# Arduino__Connectors.net
KiCad netlist of a schematic drawn in Altium Designer
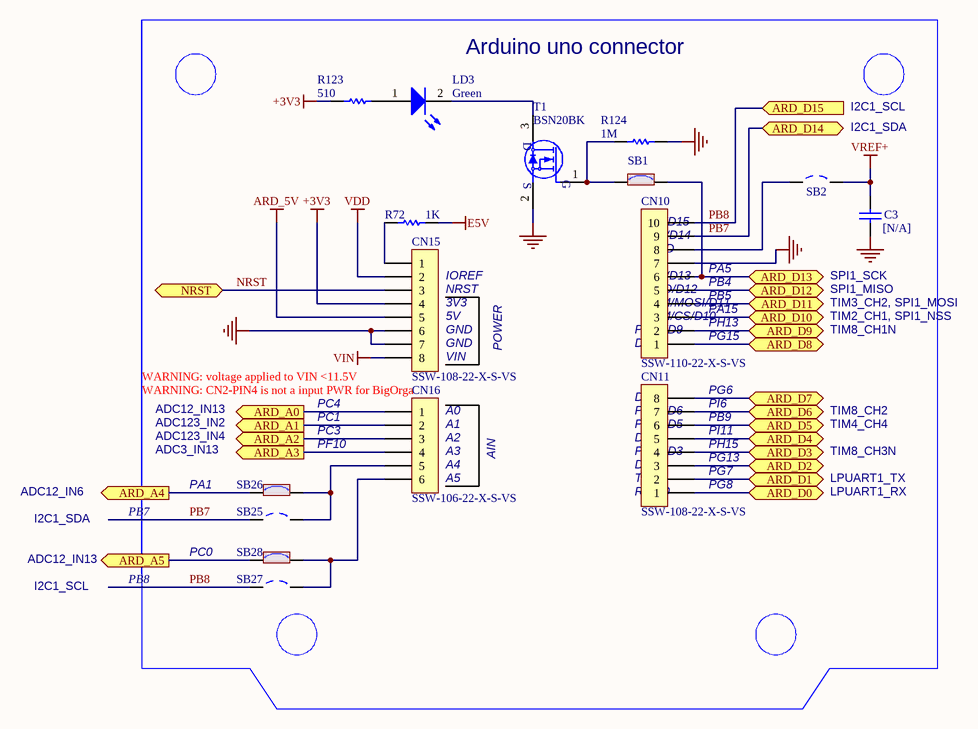
[diagram p0: Arduino_ Connectors.SchDoc]

(export (version "E")
  (design (tool "Eeschema 10.0.6"))
  (components
    (comp (ref "C3")
      (value "[N/A]")
      (footprint "0603C")
      (description "Capacitor,100nF,10%,16V,X7R,0603,YAGEO")
      (fields (field (name "PUBLISHER") "Altium Limited"))
      (libsource (lib "Miscellaneous Devices") (part "Cap"))
    )
    (comp (ref "CN10")
      (value "SSW-110-22-X-S-VS")
      (footprint "SSW-110-22-X-S-VS")
      (description "Header, 10-Pin, Single row,female")
      (fields (field (name "PUBLISHER") "Altium Limited"))
      (libsource (lib "Nucleo_64") (part "Header 10X1_Female"))
    )
    (comp (ref "CN11")
      (value "SSW-108-22-X-S-VS")
      (footprint "SSW-108-22-X-S-VS")
      (description "Header, 8-Pin, Single row,female")
      (fields (field (name "PUBLISHER") "Altium Limited"))
      (libsource (lib "Nucleo_64") (part "Header 8X1_Female"))
    )
    (comp (ref "CN15")
      (value "SSW-108-22-X-S-VS")
      (footprint "SSW-108-22-X-S-VS")
      (description "Header, 8-Pin, Single row,female")
      (fields (field (name "PUBLISHER") "Altium Limited"))
      (libsource (lib "") (part "Header 8X1_Female_1"))
    )
    (comp (ref "CN16")
      (value "SSW-106-22-X-S-VS")
      (footprint "SSW-106-22-X-S-VS")
      (description "Header, 6-Pin, Single row,female")
      (fields (field (name "PUBLISHER") "Altium Limited"))
      (libsource (lib "Nucleo_64") (part "Header 6X1_Female"))
    )
    (comp (ref "LD3")
      (value "19-213SY6C/S530-E2/TR8LED")
      (footprint "0603D")
      (description "LED,Green,0603")
      (fields (field (name "CORLOR") "Green") (field (name "PUBLISHER") "Altium Limited"))
      (libsource (lib "Miscellaneous Devices") (part "LED2"))
    )
    (comp (ref "R72")
      (value "1K")
      (footprint "0603R")
      (description "Resistor,1K,0603,1%")
      (fields (field (name "PUBLISHER") "Altium Limited"))
      (libsource (lib "Miscellaneous Devices") (part "res1"))
    )
    (comp (ref "R123")
      (value "510")
      (footprint "0603R")
      (description "Resistor, 510R , 0603,1%,YAGEO")
      (fields (field (name "Comment") "RC0603JR-07510RL") (field (name "PUBLISHER") "Altium Limited"))
      (libsource (lib "Miscellaneous Devices") (part "res1"))
    )
    (comp (ref "R124")
      (value "1M")
      (footprint "0603R")
      (description "Resistor, 1M , 0603")
      (fields (field (name "PUBLISHER") "Altium Limited"))
      (libsource (lib "Miscellaneous Devices") (part "res1"))
    )
    (comp (ref "SB1")
      (value "Solder Bridge ON")
      (footprint "SB_0603")
      (libsource (lib "MCD_TOOLS") (part "SB_ON"))
    )
    (comp (ref "SB2")
      (value "Solder Bridge OFF")
      (footprint "SB_0603")
      (libsource (lib "MCD_TOOLS") (part "SB_OFF"))
    )
    (comp (ref "SB25")
      (value "Solder Bridge OFF")
      (footprint "SB_0603")
      (libsource (lib "MCD_TOOLS") (part "SB_OFF"))
    )
    (comp (ref "SB26")
      (value "Solder Bridge ON")
      (footprint "SB_0603")
      (libsource (lib "MCD_TOOLS") (part "SB_ON"))
    )
    (comp (ref "SB27")
      (value "Solder Bridge OFF")
      (footprint "SB_0603")
      (libsource (lib "MCD_TOOLS") (part "SB_OFF"))
    )
    (comp (ref "SB28")
      (value "Solder Bridge ON")
      (footprint "SB_0603")
      (libsource (lib "MCD_TOOLS") (part "SB_ON"))
    )
    (comp (ref "T1") (value "BSN20BK") (footprint "SOT-23") (libsource (lib "MB525") (part "2N7000")))
  )
  (nets
    (net (code "1") (name "+3V3") (class "Default")
      (node (ref "CN15") (pin "4") (pinfunction "4_4") (pintype "passive"))
      (node (ref "R123") (pin "1") (pinfunction "1_1") (pintype "passive"))
    )
    (net (code "2") (name "/ARD_A0") (class "Default")
      (node (ref "CN16") (pin "1") (pinfunction "1_1") (pintype "passive"))
    )
    (net (code "3") (name "/ARD_A1") (class "Default")
      (node (ref "CN16") (pin "2") (pinfunction "2_2") (pintype "passive"))
    )
    (net (code "4") (name "/ARD_A2") (class "Default")
      (node (ref "CN16") (pin "3") (pinfunction "3_3") (pintype "passive"))
    )
    (net (code "5") (name "/ARD_A3") (class "Default")
      (node (ref "CN16") (pin "4") (pinfunction "4_4") (pintype "passive"))
    )
    (net (code "6") (name "/ARD_A4") (class "Default")
      (node (ref "SB26") (pin "1") (pinfunction "1_1") (pintype "passive"))
    )
    (net (code "7") (name "/ARD_A5") (class "Default")
      (node (ref "SB28") (pin "1") (pinfunction "1_1") (pintype "passive"))
    )
    (net (code "8") (name "/ARD_D0") (class "Default")
      (node (ref "CN11") (pin "1") (pinfunction "1_1") (pintype "passive"))
    )
    (net (code "9") (name "/ARD_D1") (class "Default")
      (node (ref "CN11") (pin "2") (pinfunction "2_2") (pintype "passive"))
    )
    (net (code "10") (name "/ARD_D2") (class "Default")
      (node (ref "CN11") (pin "3") (pinfunction "3_3") (pintype "passive"))
    )
    (net (code "11") (name "/ARD_D3") (class "Default")
      (node (ref "CN11") (pin "4") (pinfunction "4_4") (pintype "passive"))
    )
    (net (code "12") (name "/ARD_D4") (class "Default")
      (node (ref "CN11") (pin "5") (pinfunction "5_5") (pintype "passive"))
    )
    (net (code "13") (name "/ARD_D5") (class "Default")
      (node (ref "CN11") (pin "6") (pinfunction "6_6") (pintype "passive"))
    )
    (net (code "14") (name "/ARD_D6") (class "Default")
      (node (ref "CN11") (pin "7") (pinfunction "7_7") (pintype "passive"))
    )
    (net (code "15") (name "/ARD_D7") (class "Default")
      (node (ref "CN11") (pin "8") (pinfunction "8_8") (pintype "passive"))
    )
    (net (code "16") (name "/ARD_D8") (class "Default")
      (node (ref "CN10") (pin "1") (pinfunction "1_1") (pintype "passive"))
    )
    (net (code "17") (name "/ARD_D9") (class "Default")
      (node (ref "CN10") (pin "2") (pinfunction "2_2") (pintype "passive"))
    )
    (net (code "18") (name "/ARD_D10") (class "Default")
      (node (ref "CN10") (pin "3") (pinfunction "3_3") (pintype "passive"))
    )
    (net (code "19") (name "/ARD_D11") (class "Default")
      (node (ref "CN10") (pin "4") (pinfunction "4_4") (pintype "passive"))
    )
    (net (code "20") (name "/ARD_D12") (class "Default")
      (node (ref "CN10") (pin "5") (pinfunction "5_5") (pintype "passive"))
    )
    (net (code "21") (name "/ARD_D13") (class "Default")
      (node (ref "CN10") (pin "6") (pinfunction "6_6") (pintype "passive"))
      (node (ref "SB1") (pin "2") (pinfunction "2_2") (pintype "passive"))
    )
    (net (code "22") (name "/NRST") (class "Default")
      (node (ref "CN15") (pin "3") (pinfunction "3_3") (pintype "passive"))
    )
    (net (code "23") (name "/PB7") (class "Default")
      (node (ref "CN10") (pin "9") (pinfunction "9_9") (pintype "passive"))
      (node (ref "SB25") (pin "1") (pinfunction "1_1") (pintype "passive"))
    )
    (net (code "24") (name "/PB8") (class "Default")
      (node (ref "CN10") (pin "10") (pinfunction "10_10") (pintype "passive"))
      (node (ref "SB27") (pin "1") (pinfunction "1_1") (pintype "passive"))
    )
    (net (code "25") (name "ARD_5V") (class "Default")
      (node (ref "CN15") (pin "5") (pinfunction "5_5") (pintype "passive"))
    )
    (net (code "26") (name "E5V") (class "Default")
      (node (ref "R72") (pin "1") (pinfunction "1_1") (pintype "passive"))
    )
    (net (code "27") (name "GND") (class "Default")
      (node (ref "C3") (pin "2") (pinfunction "2_2") (pintype "passive"))
      (node (ref "CN10") (pin "7") (pinfunction "7_7") (pintype "passive"))
      (node (ref "CN15") (pin "6") (pinfunction "6_6") (pintype "passive"))
      (node (ref "CN15") (pin "7") (pinfunction "7_7") (pintype "passive"))
      (node (ref "R124") (pin "2") (pinfunction "2_2") (pintype "passive"))
      (node (ref "T1") (pin "2") (pinfunction "S_2") (pintype "passive"))
    )
    (net (code "28") (name "Net-(CN10-Pad8)") (class "Default")
      (node (ref "CN10") (pin "8") (pinfunction "8_8") (pintype "passive"))
      (node (ref "SB2") (pin "1") (pinfunction "1_1") (pintype "passive"))
    )
    (net (code "29") (name "Net-(CN15-Pad1)") (class "Default")
      (node (ref "CN15") (pin "1") (pinfunction "1_1") (pintype "passive"))
      (node (ref "R72") (pin "2") (pinfunction "2_2") (pintype "passive"))
    )
    (net (code "30") (name "Net-(CN16-Pad5)") (class "Default")
      (node (ref "CN16") (pin "5") (pinfunction "5_5") (pintype "passive"))
      (node (ref "SB25") (pin "2") (pinfunction "2_2") (pintype "passive"))
      (node (ref "SB26") (pin "2") (pinfunction "2_2") (pintype "passive"))
    )
    (net (code "31") (name "Net-(CN16-Pad6)") (class "Default")
      (node (ref "CN16") (pin "6") (pinfunction "6_6") (pintype "passive"))
      (node (ref "SB27") (pin "2") (pinfunction "2_2") (pintype "passive"))
      (node (ref "SB28") (pin "2") (pinfunction "2_2") (pintype "passive"))
    )
    (net (code "32") (name "Net-(LD3-A)") (class "Default")
      (node (ref "LD3") (pin "1") (pinfunction "A_1") (pintype "passive"))
      (node (ref "R123") (pin "2") (pinfunction "2_2") (pintype "passive"))
    )
    (net (code "33") (name "Net-(LD3-K)") (class "Default")
      (node (ref "LD3") (pin "2") (pinfunction "K_2") (pintype "passive"))
      (node (ref "T1") (pin "3") (pinfunction "D_3") (pintype "passive"))
    )
    (net (code "34") (name "Net-(T1-G)") (class "Default")
      (node (ref "R124") (pin "1") (pinfunction "1_1") (pintype "passive"))
      (node (ref "SB1") (pin "1") (pinfunction "1_1") (pintype "passive"))
      (node (ref "T1") (pin "1") (pinfunction "G_1") (pintype "passive"))
    )
    (net (code "35") (name "VDD") (class "Default")
      (node (ref "CN15") (pin "2") (pinfunction "2_2") (pintype "passive"))
    )
    (net (code "36") (name "VIN") (class "Default")
      (node (ref "CN15") (pin "8") (pinfunction "8_8") (pintype "passive"))
    )
    (net (code "37") (name "VREF+") (class "Default")
      (node (ref "C3") (pin "1") (pinfunction "1_1") (pintype "passive"))
      (node (ref "SB2") (pin "2") (pinfunction "2_2") (pintype "passive"))
    )
  )
)
